# EIS_Sensoren_V1_1.net
KiCad netlist of a schematic drawn in Altium Designer
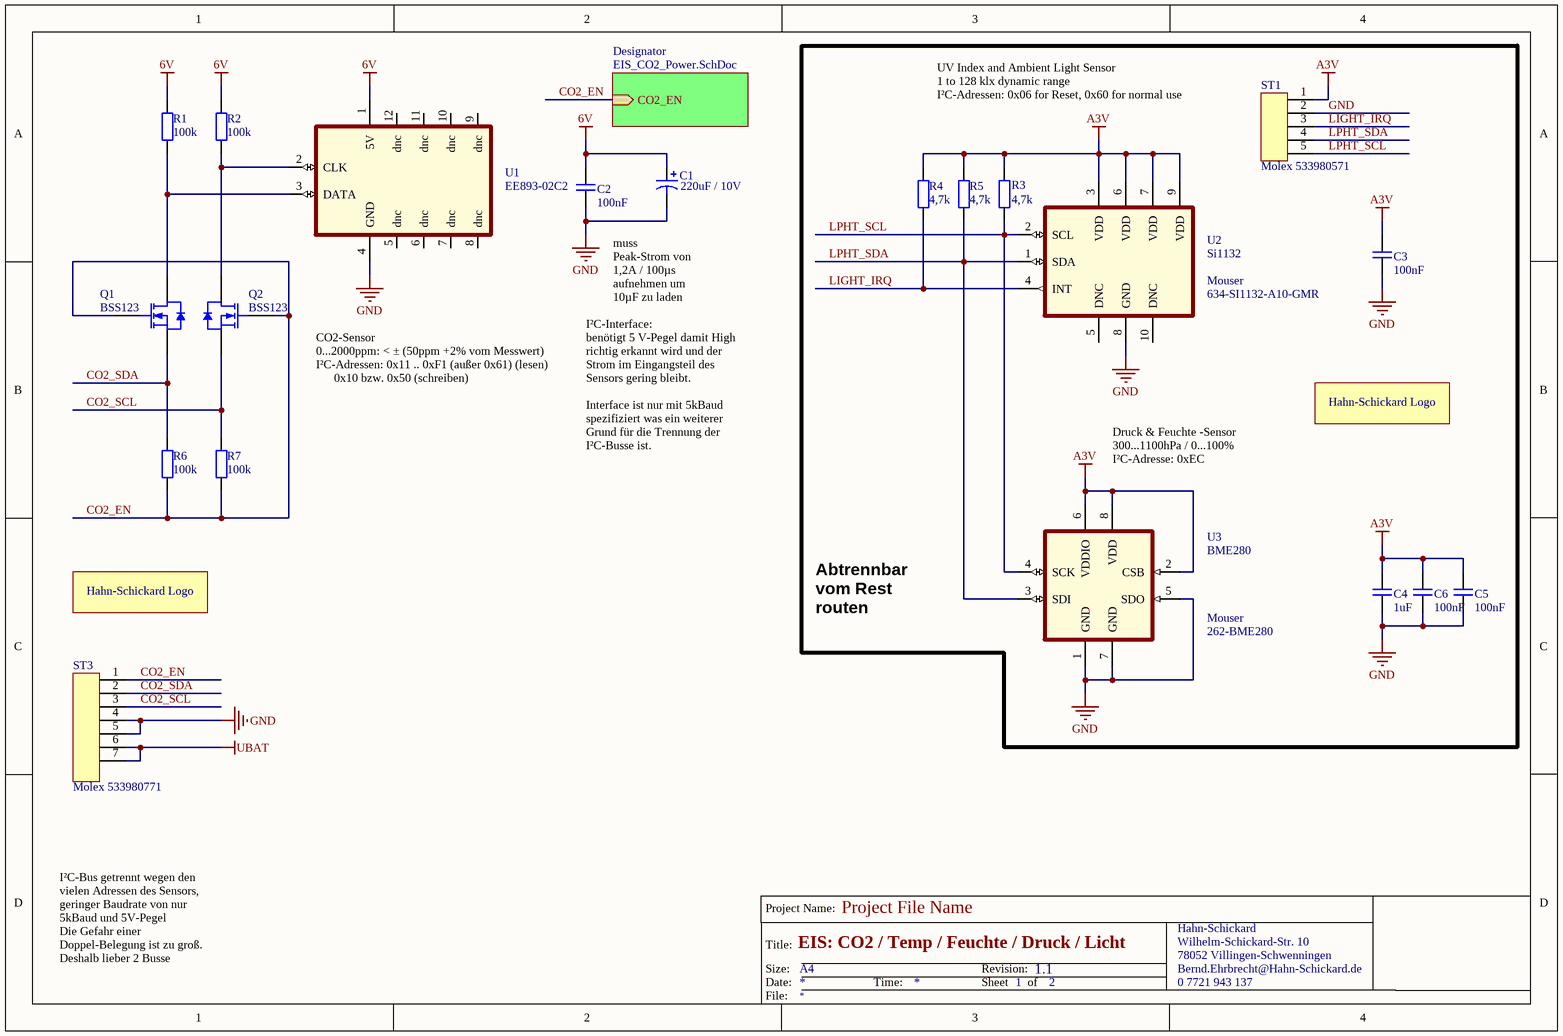
[diagram p0: EIS_Sensoren_V1_1.SchDoc]

(export (version "E")
  (design (tool "Eeschema 10.0.6"))
  (components
    (comp (ref "C1")
      (value "220uF / 10V")
      (footprint "D")
      (description "Polarized Capacitor (Surface Mount)")
      (fields (field (name "PUBLISHER") "Altium Limited"))
      (libsource (lib "Miscellaneous Devices") (part "Cap Pol3"))
    )
    (comp (ref "C2")
      (value "100nF")
      (footprint "CAPC1608N")
      (libsource (lib "My_Schlib_6_18") (part "Kondensator SMD Keramik"))
    )
    (comp (ref "C3")
      (value "100nF")
      (footprint "CAPC1608N")
      (libsource (lib "My_Schlib_6_18") (part "Kondensator SMD Keramik"))
    )
    (comp (ref "C4")
      (value "1uF")
      (footprint "CAPC3216N")
      (libsource (lib "My_Schlib_6_18") (part "Kondensator SMD Keramik"))
    )
    (comp (ref "C5")
      (value "100nF")
      (footprint "CAPC1608N")
      (libsource (lib "My_Schlib_6_18") (part "Kondensator SMD Keramik"))
    )
    (comp (ref "C6")
      (value "100nF")
      (footprint "CAPC1608N")
      (libsource (lib "My_Schlib_6_18") (part "Kondensator SMD Keramik"))
    )
    (comp (ref "LOGO1")
      (value "Hahn-Schickard LOGO")
      (footprint "Hahn-Schickard-LOGO_klein")
      (description "Hahn-Schickard Logo als Footprint")
      (libsource (lib "Eis_Lib") (part "Hahn-Schickard LOGO"))
    )
    (comp (ref "LOGO2")
      (value "Hahn-Schickard LOGO")
      (footprint "Hahn-Schickard-LOGO_klein")
      (description "Hahn-Schickard Logo als Footprint")
      (libsource (lib "Eis_Lib") (part "Hahn-Schickard LOGO"))
    )
    (comp (ref "Q1")
      (value "BSS123")
      (footprint "SOT23_N - BSS123")
      (description "N-channel Enhancement Mode Vertical D-MOSFET")
      (fields (field (name "PUBLISHER") "Altium Limited"))
      (libsource (lib "Philips Discrete MOSFET - Low Power") (part "BSS123"))
    )
    (comp (ref "Q2")
      (value "BSS123")
      (footprint "SOT23_N - BSS123")
      (description "N-channel Enhancement Mode Vertical D-MOSFET")
      (fields (field (name "PUBLISHER") "Altium Limited"))
      (libsource (lib "Philips Discrete MOSFET - Low Power") (part "BSS123"))
    )
    (comp (ref "R1")
      (value "100k")
      (footprint "RESC1608N")
      (description "RESC1608 (R0603)")
      (fields (field (name "PUBLISHER") "HSG Jürgen Merz"))
      (libsource (lib "MetaSensClampOn_BT") (part "RESC1608 (R0603)"))
    )
    (comp (ref "R2")
      (value "100k")
      (footprint "RESC1608N")
      (description "RESC1608 (R0603)")
      (fields (field (name "PUBLISHER") "HSG Jürgen Merz"))
      (libsource (lib "MetaSensClampOn_BT") (part "RESC1608 (R0603)"))
    )
    (comp (ref "R3")
      (value "4,7k")
      (footprint "RESC1608N")
      (description "RESC1608 (R0603)")
      (fields (field (name "PUBLISHER") "HSG Jürgen Merz"))
      (libsource (lib "MetaSensClampOn_BT") (part "RESC1608 (R0603)"))
    )
    (comp (ref "R4")
      (value "4,7k")
      (footprint "RESC1608N")
      (description "RESC1608 (R0603)")
      (fields (field (name "PUBLISHER") "HSG Jürgen Merz"))
      (libsource (lib "MetaSensClampOn_BT") (part "RESC1608 (R0603)"))
    )
    (comp (ref "R5")
      (value "4,7k")
      (footprint "RESC1608N")
      (description "RESC1608 (R0603)")
      (fields (field (name "PUBLISHER") "HSG Jürgen Merz"))
      (libsource (lib "MetaSensClampOn_BT") (part "RESC1608 (R0603)"))
    )
    (comp (ref "R6")
      (value "100k")
      (footprint "RESC1608N")
      (description "RESC1608 (R0603)")
      (fields (field (name "PUBLISHER") "HSG Jürgen Merz"))
      (libsource (lib "MetaSensClampOn_BT") (part "RESC1608 (R0603)"))
    )
    (comp (ref "R7")
      (value "100k")
      (footprint "RESC1608N")
      (description "RESC1608 (R0603)")
      (fields (field (name "PUBLISHER") "HSG Jürgen Merz"))
      (libsource (lib "MetaSensClampOn_BT") (part "RESC1608 (R0603)"))
    )
    (comp (ref "ST1")
      (value "Molex 533980571")
      (footprint "Molex 533980571")
      (description "MOLEX - 53398-0571 - STIFTLEISTE, SMT, 1.25MM, 5POL")
      (libsource (lib "JM_Elektromechanik") (part "Molex 533980571"))
    )
    (comp (ref "ST3")
      (value "Molex 533980771")
      (footprint "Molex 533980771")
      (description "Molex Pico 7Pol Blade SMD gerade 533980771")
      (libsource (lib "JM_Elektromechanik") (part "Molex 533980771"))
    )
    (comp (ref "U1")
      (value "EE893-02C2")
      (footprint "EE893")
      (description "CO2-Sensor; I²C-Interface,")
      (libsource (lib "Eis_Lib") (part "EE893-02C2"))
    )
    (comp (ref "U2")
      (value "Si1132")
      (footprint "Si1132")
      (description "UV INDEX AND AMBIENT LIGHT SENSOR IC WITH I2C INTERFACE, QFN 2x2mm")
      (fields
        (field (name "SUPPLIER 1") "Mouser")
        (field (name "SUPPLIER PART NUMBER 1") "634-SI1132-A10-GMR")
      )
      (libsource (lib "Eis_Lib") (part "Si1132"))
    )
    (comp (ref "U3")
      (value "BME280")
      (footprint "BME280")
      (description "Bosch, Druck & Feuchte-Sensor, I2C / SPI")
      (fields (field (name "SUPPLIER 1") "Mouser") (field (name "SUPPLIER PART NUMBER 1") "262-BME280"))
      (libsource (lib "Eis_Lib") (part "BME280"))
    )
  )
  (nets
    (net (code "1") (name "/CO2_EN") (class "Default")
      (node (ref "Q1") (pin "1") (pinfunction "G_1") (pintype "passive"))
      (node (ref "Q2") (pin "1") (pinfunction "G_1") (pintype "passive"))
      (node (ref "R6") (pin "1") (pinfunction "1_1") (pintype "passive"))
      (node (ref "R7") (pin "1") (pinfunction "1_1") (pintype "passive"))
      (node (ref "ST3") (pin "1") (pinfunction "1_1") (pintype "passive"))
    )
    (net (code "2") (name "/CO2_SCL") (class "Default")
      (node (ref "Q2") (pin "2") (pinfunction "S_2") (pintype "passive"))
      (node (ref "R7") (pin "2") (pinfunction "2_2") (pintype "passive"))
      (node (ref "ST3") (pin "3") (pinfunction "3_3") (pintype "passive"))
    )
    (net (code "3") (name "/CO2_SDA") (class "Default")
      (node (ref "Q1") (pin "2") (pinfunction "S_2") (pintype "passive"))
      (node (ref "R6") (pin "2") (pinfunction "2_2") (pintype "passive"))
      (node (ref "ST3") (pin "2") (pinfunction "2_2") (pintype "passive"))
    )
    (net (code "4") (name "/LIGHT_IRQ") (class "Default")
      (node (ref "R4") (pin "1") (pinfunction "1_1") (pintype "passive"))
      (node (ref "ST1") (pin "3") (pinfunction "3_3") (pintype "passive"))
      (node (ref "U2") (pin "4") (pinfunction "INT_4") (pintype "output"))
    )
    (net (code "5") (name "/LPHT_SCL") (class "Default")
      (node (ref "R3") (pin "1") (pinfunction "1_1") (pintype "passive"))
      (node (ref "ST1") (pin "5") (pinfunction "5_5") (pintype "passive"))
      (node (ref "U2") (pin "2") (pinfunction "SCL_2") (pintype "bidirectional"))
      (node (ref "U3") (pin "4") (pinfunction "SCK_4") (pintype "bidirectional"))
    )
    (net (code "6") (name "/LPHT_SDA") (class "Default")
      (node (ref "R5") (pin "1") (pinfunction "1_1") (pintype "passive"))
      (node (ref "ST1") (pin "4") (pinfunction "4_4") (pintype "passive"))
      (node (ref "U2") (pin "1") (pinfunction "SDA_1") (pintype "bidirectional"))
      (node (ref "U3") (pin "3") (pinfunction "SDI_3") (pintype "bidirectional"))
    )
    (net (code "7") (name "6V") (class "Default")
      (node (ref "C1") (pin "1") (pinfunction "1_1") (pintype "passive"))
      (node (ref "C2") (pin "1") (pinfunction "1_1") (pintype "passive"))
      (node (ref "R1") (pin "2") (pinfunction "2_2") (pintype "passive"))
      (node (ref "R2") (pin "2") (pinfunction "2_2") (pintype "passive"))
      (node (ref "U1") (pin "1") (pinfunction "5V_1") (pintype "power_in"))
    )
    (net (code "8") (name "A3V") (class "Default")
      (node (ref "C3") (pin "1") (pinfunction "1_1") (pintype "passive"))
      (node (ref "C4") (pin "1") (pinfunction "1_1") (pintype "passive"))
      (node (ref "C5") (pin "1") (pinfunction "1_1") (pintype "passive"))
      (node (ref "C6") (pin "1") (pinfunction "1_1") (pintype "passive"))
      (node (ref "R3") (pin "2") (pinfunction "2_2") (pintype "passive"))
      (node (ref "R4") (pin "2") (pinfunction "2_2") (pintype "passive"))
      (node (ref "R5") (pin "2") (pinfunction "2_2") (pintype "passive"))
      (node (ref "ST1") (pin "1") (pinfunction "1_1") (pintype "passive"))
      (node (ref "U2") (pin "3") (pinfunction "VDD_3") (pintype "power_in"))
      (node (ref "U2") (pin "6") (pinfunction "VDD_6") (pintype "power_in"))
      (node (ref "U2") (pin "7") (pinfunction "VDD_7") (pintype "power_in"))
      (node (ref "U2") (pin "9") (pinfunction "VDD_9") (pintype "power_in"))
      (node (ref "U3") (pin "2") (pinfunction "CSB_2") (pintype "input"))
      (node (ref "U3") (pin "6") (pinfunction "VDDIO_6") (pintype "power_in"))
      (node (ref "U3") (pin "8") (pinfunction "VDD_8") (pintype "power_in"))
    )
    (net (code "9") (name "GND") (class "Default")
      (node (ref "C1") (pin "2") (pinfunction "2_2") (pintype "passive"))
      (node (ref "C2") (pin "2") (pinfunction "2_2") (pintype "passive"))
      (node (ref "C3") (pin "2") (pinfunction "2_2") (pintype "passive"))
      (node (ref "C4") (pin "2") (pinfunction "2_2") (pintype "passive"))
      (node (ref "C5") (pin "2") (pinfunction "2_2") (pintype "passive"))
      (node (ref "C6") (pin "2") (pinfunction "2_2") (pintype "passive"))
      (node (ref "ST1") (pin "2") (pinfunction "2_2") (pintype "passive"))
      (node (ref "ST3") (pin "4") (pinfunction "4_4") (pintype "passive"))
      (node (ref "ST3") (pin "5") (pinfunction "5_5") (pintype "passive"))
      (node (ref "U1") (pin "4") (pinfunction "GND_4") (pintype "power_in"))
      (node (ref "U2") (pin "8") (pinfunction "GND_8") (pintype "power_in"))
      (node (ref "U3") (pin "1") (pinfunction "GND_1") (pintype "power_in"))
      (node (ref "U3") (pin "5") (pinfunction "SDO_5") (pintype "input"))
      (node (ref "U3") (pin "7") (pinfunction "GND_7") (pintype "power_in"))
    )
    (net (code "10") (name "Net-(Q1-D)") (class "Default")
      (node (ref "Q1") (pin "3") (pinfunction "D_3") (pintype "passive"))
      (node (ref "R1") (pin "1") (pinfunction "1_1") (pintype "passive"))
      (node (ref "U1") (pin "3") (pinfunction "DATA_3") (pintype "bidirectional"))
    )
    (net (code "11") (name "Net-(Q2-D)") (class "Default")
      (node (ref "Q2") (pin "3") (pinfunction "D_3") (pintype "passive"))
      (node (ref "R2") (pin "1") (pinfunction "1_1") (pintype "passive"))
      (node (ref "U1") (pin "2") (pinfunction "CLK_2") (pintype "bidirectional"))
    )
    (net (code "12") (name "UBAT") (class "Default")
      (node (ref "ST3") (pin "6") (pinfunction "6_6") (pintype "passive"))
      (node (ref "ST3") (pin "7") (pinfunction "7_7") (pintype "passive"))
    )
    (net (code "13") (name "unconnected-(ST1-Pad6)") (class "Default")
      (node (ref "ST1") (pin "6") (pinfunction "6_6") (pintype "passive"))
    )
    (net (code "14") (name "unconnected-(ST1-Pad7)") (class "Default")
      (node (ref "ST1") (pin "7") (pinfunction "7_7") (pintype "passive"))
    )
    (net (code "15") (name "unconnected-(ST3-Pad8)") (class "Default")
      (node (ref "ST3") (pin "8") (pinfunction "8_8") (pintype "passive"))
    )
    (net (code "16") (name "unconnected-(ST3-Pad9)") (class "Default")
      (node (ref "ST3") (pin "9") (pinfunction "9_9") (pintype "passive"))
    )
    (net (code "17") (name "unconnected-(U1-dnc-Pad5)") (class "Default")
      (node (ref "U1") (pin "5") (pinfunction "dnc_5") (pintype "passive"))
    )
    (net (code "18") (name "unconnected-(U1-dnc-Pad6)") (class "Default")
      (node (ref "U1") (pin "6") (pinfunction "dnc_6") (pintype "passive"))
    )
    (net (code "19") (name "unconnected-(U1-dnc-Pad7)") (class "Default")
      (node (ref "U1") (pin "7") (pinfunction "dnc_7") (pintype "passive"))
    )
    (net (code "20") (name "unconnected-(U1-dnc-Pad8)") (class "Default")
      (node (ref "U1") (pin "8") (pinfunction "dnc_8") (pintype "passive"))
    )
    (net (code "21") (name "unconnected-(U1-dnc-Pad9)") (class "Default")
      (node (ref "U1") (pin "9") (pinfunction "dnc_9") (pintype "passive"))
    )
    (net (code "22") (name "unconnected-(U1-dnc-Pad10)") (class "Default")
      (node (ref "U1") (pin "10") (pinfunction "dnc_10") (pintype "passive"))
    )
    (net (code "23") (name "unconnected-(U1-dnc-Pad11)") (class "Default")
      (node (ref "U1") (pin "11") (pinfunction "dnc_11") (pintype "passive"))
    )
    (net (code "24") (name "unconnected-(U1-dnc-Pad12)") (class "Default")
      (node (ref "U1") (pin "12") (pinfunction "dnc_12") (pintype "passive"))
    )
    (net (code "25") (name "unconnected-(U2-DNC-Pad5)") (class "Default")
      (node (ref "U2") (pin "5") (pinfunction "DNC_5") (pintype "passive"))
    )
    (net (code "26") (name "unconnected-(U2-DNC-Pad10)") (class "Default")
      (node (ref "U2") (pin "10") (pinfunction "DNC_10") (pintype "passive"))
    )
  )
)
